# design.net
KiCad netlist of a schematic drawn in Altium Designer
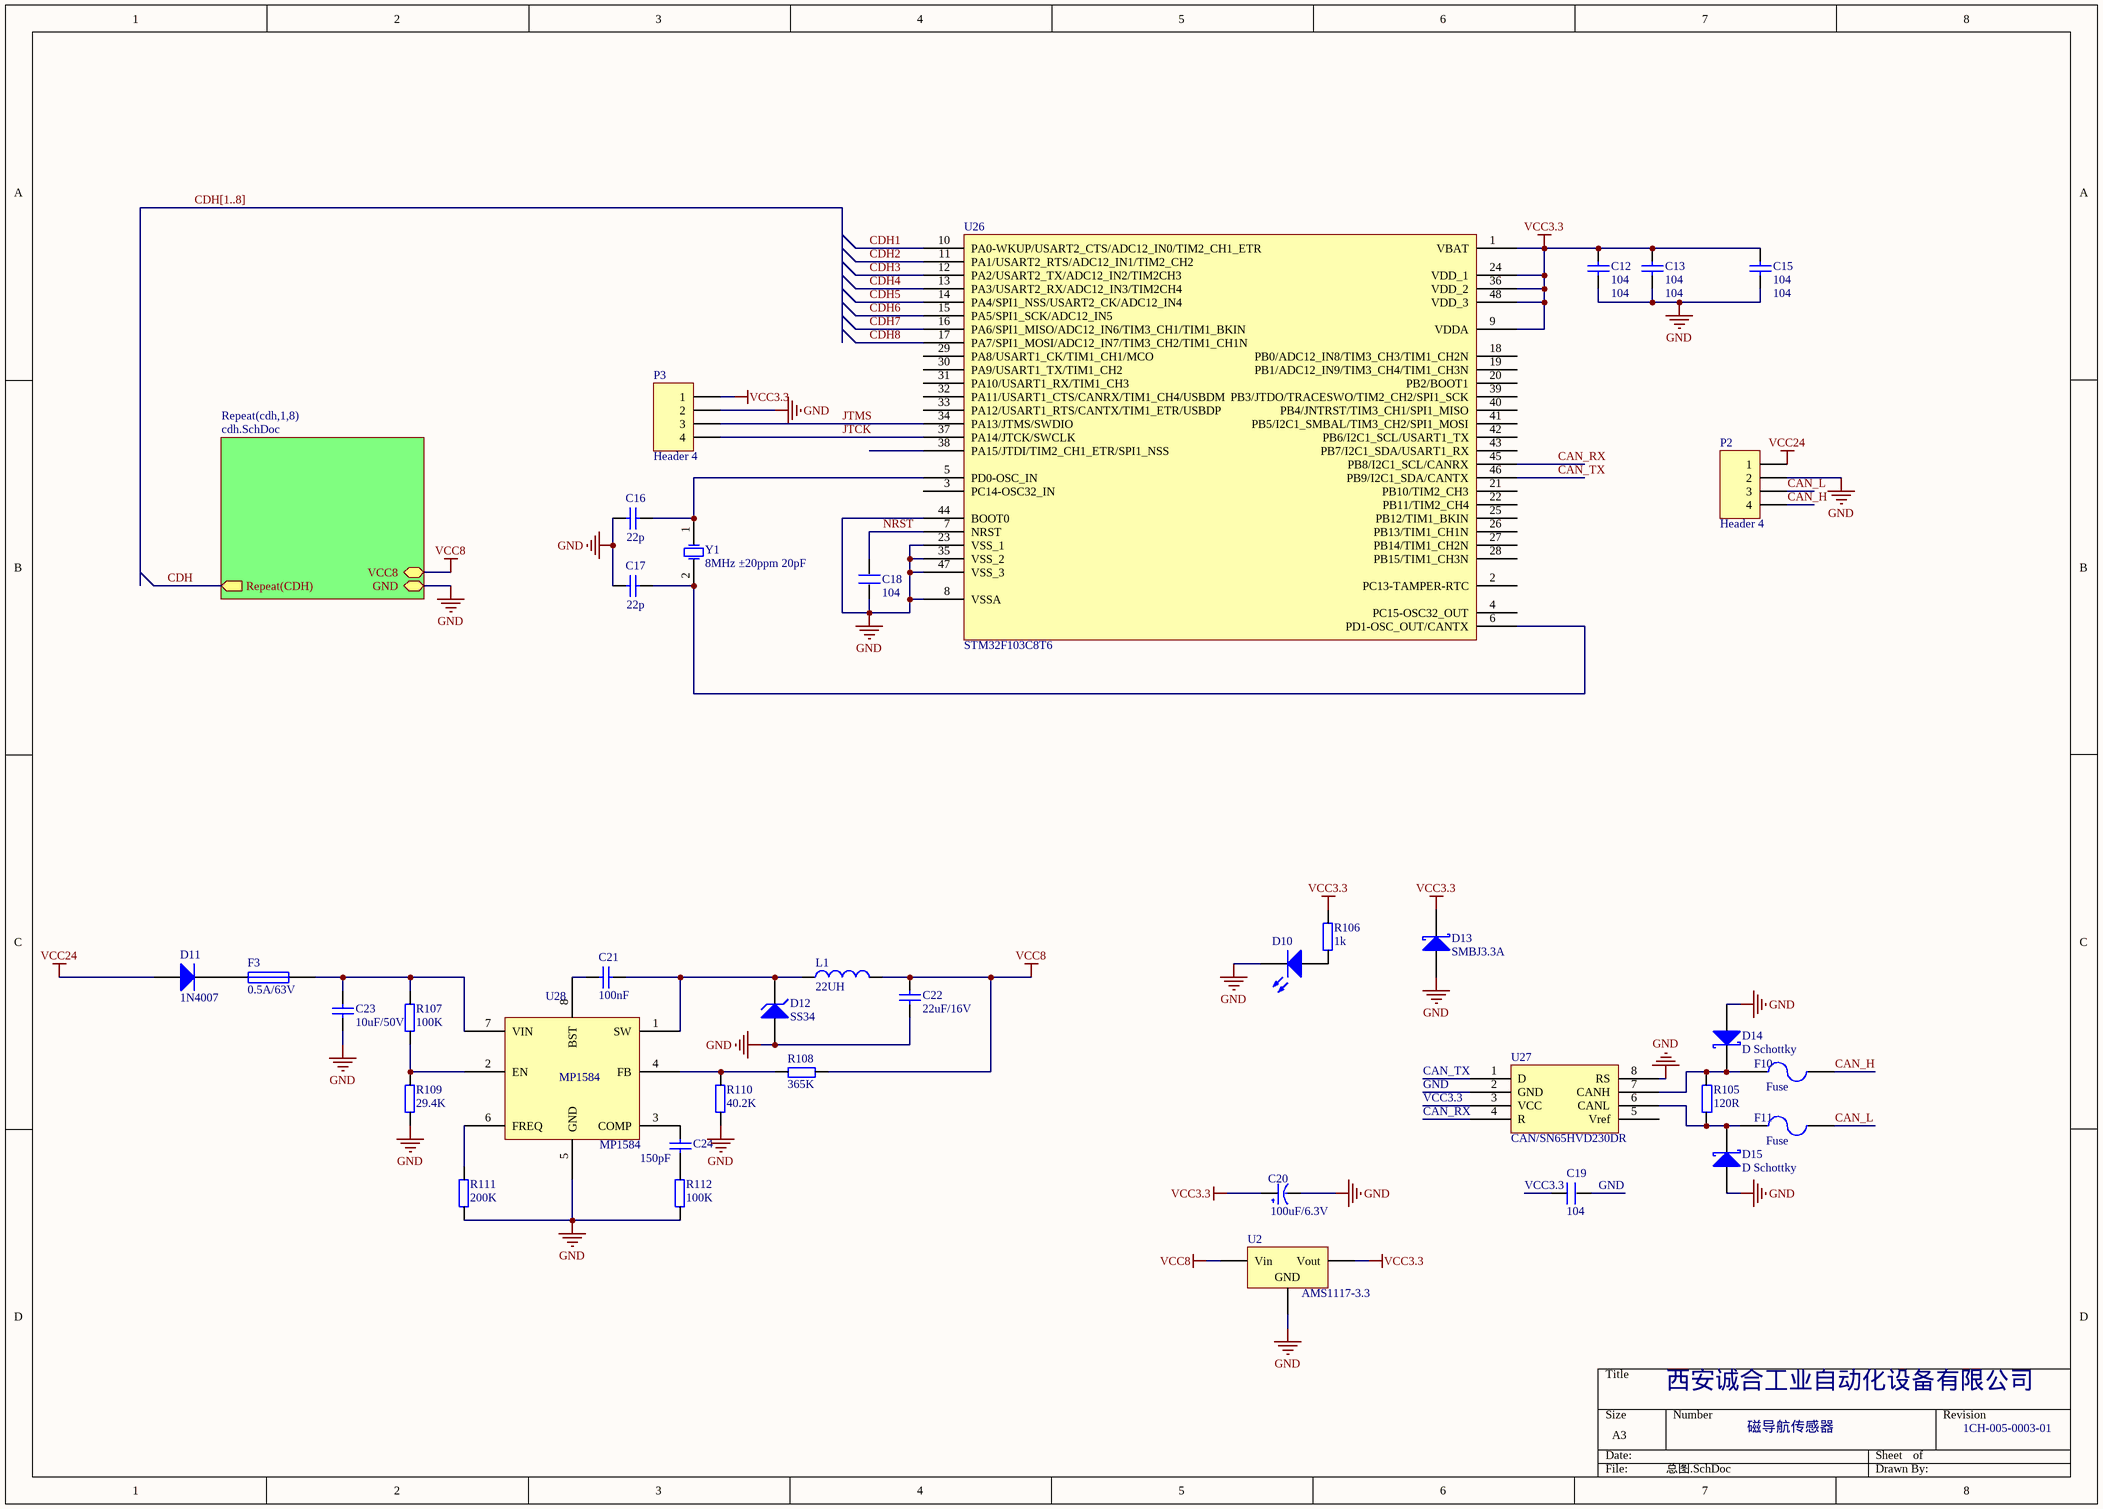
[diagram p0: 总图.SchDoc]

(export (version "E")
  (design (tool "Eeschema 10.0.6"))
  (components
    (comp (ref "C12")
      (value "104")
      (footprint "0603-CAP")
      (description "Capacitor")
      (fields (field (name "ALTIUM_VALUE") "104") (field (name "PUBLISHER") "Altium Limited"))
      (libsource (lib "Miscellaneous Devices") (part "Cap"))
    )
    (comp (ref "C13")
      (value "104")
      (footprint "0603-CAP")
      (description "Capacitor")
      (fields (field (name "ALTIUM_VALUE") "104") (field (name "PUBLISHER") "Altium Limited"))
      (libsource (lib "Miscellaneous Devices") (part "Cap"))
    )
    (comp (ref "C15")
      (value "104")
      (footprint "0603-CAP")
      (description "Capacitor")
      (fields (field (name "ALTIUM_VALUE") "104") (field (name "PUBLISHER") "Altium Limited"))
      (libsource (lib "Miscellaneous Devices") (part "Cap"))
    )
    (comp (ref "C16")
      (value "22p")
      (footprint "0603-CAP")
      (description "Capacitor")
      (fields (field (name "PUBLISHER") "Altium Limited"))
      (libsource (lib "Miscellaneous Devices") (part "Cap"))
    )
    (comp (ref "C17")
      (value "22p")
      (footprint "0603-CAP")
      (description "Capacitor")
      (fields (field (name "PUBLISHER") "Altium Limited"))
      (libsource (lib "Miscellaneous Devices") (part "Cap"))
    )
    (comp (ref "C18")
      (value "104")
      (footprint "0603-CAP")
      (libsource (lib "Explorer STM32F407封装库") (part "C"))
    )
    (comp (ref "C19")
      (value "104")
      (footprint "0603-CAP")
      (libsource (lib "Explorer STM32F407封装库") (part "C_3"))
    )
    (comp (ref "C20") (value "100uF/6.3V") (footprint "3216") (libsource (lib "WarShip V3_SCH") (part "CAP")))
    (comp (ref "C21")
      (value "100nF")
      (footprint "0603-CAP")
      (description "Capacitor (Semiconductor SIM Model)")
      (fields (field (name "Comment") "0.1uF") (field (name "PUBLISHER") "Altium Limited"))
      (libsource (lib "Miscellaneous Devices") (part "Cap Semi"))
    )
    (comp (ref "C22")
      (value "22uF/16V")
      (footprint "1206")
      (description "Capacitor (Semiconductor SIM Model)")
      (fields (field (name "PUBLISHER") "Altium Limited"))
      (libsource (lib "Miscellaneous Devices") (part "Cap Semi"))
    )
    (comp (ref "C23")
      (value "10uF/50V")
      (footprint "1206")
      (description "Capacitor (Semiconductor SIM Model)")
      (fields (field (name "PUBLISHER") "Altium Limited"))
      (libsource (lib "Miscellaneous Devices") (part "Cap Semi"))
    )
    (comp (ref "C24")
      (value "150pF")
      (footprint "0603-CAP")
      (description "Capacitor (Semiconductor SIM Model)")
      (fields (field (name "Comment") "0.1uF") (field (name "PUBLISHER") "Altium Limited"))
      (libsource (lib "Miscellaneous Devices") (part "Cap Semi"))
    )
    (comp (ref "D10")
      (value "LED0")
      (footprint "LC-0805_LED_S1")
      (description "Typical INFRARED GaAs LED")
      (fields (field (name "PUBLISHER") "Altium Limited"))
      (libsource (lib "继电器板_1") (part "LED0"))
    )
    (comp (ref "D11")
      (value "1N4007")
      (footprint "SMA(DO-214AC)_S1")
      (description "Default Diode")
      (fields (field (name "PUBLISHER") "Altium Limited"))
      (libsource (lib "Miscellaneous Devices") (part "Diode"))
    )
    (comp (ref "D12")
      (value "SS34")
      (footprint "SMA(DO-214AC)_S1")
      (description "Zener Diode")
      (fields (field (name "PUBLISHER") "Altium Limited"))
      (libsource (lib "Miscellaneous Devices") (part "D Zener"))
    )
    (comp (ref "D13")
      (value "SMBJ3.3A")
      (footprint "SMB(DO-214AA)_S1")
      (description "Schottky Rectifier")
      (fields (field (name "PUBLISHER") "Altium Limited"))
      (libsource (lib "Miscellaneous Devices") (part "Diode 18TQ045"))
    )
    (comp (ref "D14")
      (value "D Schottky")
      (footprint "SMB")
      (description "Schottky Diode")
      (fields (field (name "PUBLISHER") "Altium Limited"))
      (libsource (lib "Miscellaneous Devices") (part "D Schottky"))
    )
    (comp (ref "D15")
      (value "D Schottky")
      (footprint "SMB")
      (description "Schottky Diode")
      (fields (field (name "PUBLISHER") "Altium Limited"))
      (libsource (lib "Miscellaneous Devices") (part "D Schottky"))
    )
    (comp (ref "F3")
      (value "0.5A/63V")
      (footprint "1206")
      (description "Fuse")
      (fields (field (name "PUBLISHER") "Altium Limited"))
      (libsource (lib "Miscellaneous Devices") (part "Fuse 1"))
    )
    (comp (ref "F10")
      (value "Fuse")
      (footprint "12Z-2010")
      (fields (field (name "PUBLISHER") "Altium Limited"))
      (libsource (lib "Miscellaneous Devices") (part "Fuse 2"))
    )
    (comp (ref "F11")
      (value "Fuse")
      (footprint "12Z-2010")
      (fields (field (name "PUBLISHER") "Altium Limited"))
      (libsource (lib "Miscellaneous Devices") (part "Fuse 2"))
    )
    (comp (ref "L1")
      (value "22UH")
      (footprint "L-7*7*4mm-S")
      (description "Inductor")
      (fields (field (name "PUBLISHER") "Altium Limited"))
      (libsource (lib "Miscellaneous Devices") (part "Inductor"))
    )
    (comp (ref "P2")
      (value "Header 4")
      (footprint "DZ-4-3.5")
      (description "Header, 4-Pin")
      (fields (field (name "PUBLISHER") "Altium Limited"))
      (libsource (lib "Miscellaneous Connectors") (part "Header 4"))
    )
    (comp (ref "P3")
      (value "Header 4")
      (footprint "HDR1X4")
      (description "Header, 4-Pin")
      (fields (field (name "PUBLISHER") "Altium Limited"))
      (libsource (lib "Miscellaneous Connectors") (part "Header 4"))
    )
    (comp (ref "R105")
      (value "120R")
      (footprint "0805_R")
      (libsource (lib "Explorer STM32F407封装库") (part "R_2"))
    )
    (comp (ref "R106") (value "1k") (footprint "0603") (libsource (lib "Explorer STM32F407封装库") (part "R_2")))
    (comp (ref "R107")
      (value "100K")
      (footprint "0603")
      (libsource (lib "Explorer STM32F407封装库") (part "R_2"))
    )
    (comp (ref "R108")
      (value "365K")
      (footprint "0603")
      (libsource (lib "Explorer STM32F407封装库") (part "R_2"))
    )
    (comp (ref "R109")
      (value "29.4K")
      (footprint "0603")
      (libsource (lib "Explorer STM32F407封装库") (part "R_2"))
    )
    (comp (ref "R110")
      (value "40.2K")
      (footprint "0603")
      (libsource (lib "Explorer STM32F407封装库") (part "R_2"))
    )
    (comp (ref "R111")
      (value "200K")
      (footprint "0603")
      (libsource (lib "Explorer STM32F407封装库") (part "R_2"))
    )
    (comp (ref "R112")
      (value "100K")
      (footprint "0603")
      (libsource (lib "Explorer STM32F407封装库") (part "R_2"))
    )
    (comp (ref "U2")
      (value "AMS1117-3.3")
      (footprint "SOT-223")
      (description "低压差线性稳压(LDO)")
      (libsource (lib "Miscellaneous Devices LC") (part "SOT-223 AMS1117-3.3"))
    )
    (comp (ref "U26")
      (value "STM32F103C8T6")
      (footprint "LC-LQFP-48")
      (libsource (lib "Schlib1") (part "stm32f103v8t6"))
    )
    (comp (ref "U27")
      (value "CAN/SN65HVD230DR")
      (footprint "SOIC-8_150mil")
      (description "CAN")
      (libsource (lib "Miscellaneous Devices LC") (part "CAN/SN65HVD230DR_[C12084]"))
    )
    (comp (ref "U28") (value "MP1584") (footprint "SO-8") (libsource (lib "磁导航") (part "MP1584EN")))
    (comp (ref "Y1")
      (value "8MHz ±20ppm 20pF")
      (footprint "SMD-5032_2P")
      (description "贴片晶振")
      (libsource (lib "Miscellaneous Devices LC") (part "SMD-5032_2P 8MHz 20ppm 20pF"))
    )
  )
  (nets
    (net (code "1") (name "/CAN_H") (class "Default")
      (node (ref "F10") (pin "1") (pinfunction "1_1") (pintype "passive"))
      (node (ref "P2") (pin "4") (pinfunction "4_4") (pintype "passive"))
    )
    (net (code "2") (name "/CAN_L") (class "Default")
      (node (ref "F11") (pin "1") (pinfunction "1_1") (pintype "passive"))
      (node (ref "P2") (pin "3") (pinfunction "3_3") (pintype "passive"))
    )
    (net (code "3") (name "/CAN_RX") (class "Default")
      (node (ref "U26") (pin "45") (pinfunction "PB8/I2C1_SCL/CANRX_45") (pintype "passive"))
      (node (ref "U27") (pin "4") (pinfunction "R_4") (pintype "passive"))
    )
    (net (code "4") (name "/CAN_TX") (class "Default")
      (node (ref "U26") (pin "46") (pinfunction "PB9/I2C1_SDA/CANTX_46") (pintype "passive"))
      (node (ref "U27") (pin "1") (pinfunction "D_1") (pintype "passive"))
    )
    (net (code "6") (name "/CDH1") (class "Default")
      (node (ref "U26") (pin "10") (pinfunction "PA0-WKUP/USART2_CTS/ADC12_IN0/TIM2_CH1_ETR_10") (pintype "passive"))
    )
    (net (code "7") (name "/CDH2") (class "Default")
      (node (ref "U26") (pin "11") (pinfunction "PA1/USART2_RTS/ADC12_IN1/TIM2_CH2_11") (pintype "passive"))
    )
    (net (code "8") (name "/CDH3") (class "Default")
      (node (ref "U26") (pin "12") (pinfunction "PA2/USART2_TX/ADC12_IN2/TIM2CH3_12") (pintype "passive"))
    )
    (net (code "9") (name "/CDH4") (class "Default")
      (node (ref "U26") (pin "13") (pinfunction "PA3/USART2_RX/ADC12_IN3/TIM2CH4_13") (pintype "passive"))
    )
    (net (code "10") (name "/CDH5") (class "Default")
      (node (ref "U26") (pin "14") (pinfunction "PA4/SPI1_NSS/USART2_CK/ADC12_IN4_14") (pintype "passive"))
    )
    (net (code "11") (name "/CDH6") (class "Default")
      (node (ref "U26") (pin "15") (pinfunction "PA5/SPI1_SCK/ADC12_IN5_15") (pintype "passive"))
    )
    (net (code "12") (name "/CDH7") (class "Default")
      (node (ref "U26") (pin "16") (pinfunction "PA6/SPI1_MISO/ADC12_IN6/TIM3_CH1/TIM1_BKIN_16") (pintype "passive"))
    )
    (net (code "13") (name "/CDH8") (class "Default")
      (node (ref "U26") (pin "17") (pinfunction "PA7/SPI1_MOSI/ADC12_IN7/TIM3_CH2/TIM1_CH1N_17") (pintype "passive"))
    )
    (net (code "15") (name "/JTCK") (class "Default")
      (node (ref "P3") (pin "4") (pinfunction "4_4") (pintype "passive"))
      (node (ref "U26") (pin "37") (pinfunction "PA14/JTCK/SWCLK_37") (pintype "passive"))
    )
    (net (code "16") (name "/JTMS") (class "Default")
      (node (ref "P3") (pin "3") (pinfunction "3_3") (pintype "passive"))
      (node (ref "U26") (pin "34") (pinfunction "PA13/JTMS/SWDIO_34") (pintype "passive"))
    )
    (net (code "17") (name "/NRST") (class "Default")
      (node (ref "C18") (pin "2") (pintype "passive"))
      (node (ref "U26") (pin "7") (pinfunction "NRST_7") (pintype "passive"))
    )
    (net (code "18") (name "GND") (class "Default")
      (node (ref "C12") (pin "2") (pinfunction "2_2") (pintype "passive"))
      (node (ref "C13") (pin "2") (pinfunction "2_2") (pintype "passive"))
      (node (ref "C15") (pin "2") (pinfunction "2_2") (pintype "passive"))
      (node (ref "C16") (pin "2") (pinfunction "2_2") (pintype "passive"))
      (node (ref "C17") (pin "2") (pinfunction "2_2") (pintype "passive"))
      (node (ref "C18") (pin "1") (pintype "passive"))
      (node (ref "C19") (pin "2") (pintype "passive"))
      (node (ref "C20") (pin "2") (pinfunction "GND_2") (pintype "passive"))
      (node (ref "C22") (pin "1") (pinfunction "1_1") (pintype "passive"))
      (node (ref "C23") (pin "2") (pinfunction "2_2") (pintype "passive"))
      (node (ref "D10") (pin "K") (pinfunction "K_K") (pintype "passive"))
      (node (ref "D12") (pin "1") (pinfunction "A_1") (pintype "passive"))
      (node (ref "D13") (pin "2") (pinfunction "A_2") (pintype "passive"))
      (node (ref "D14") (pin "1") (pinfunction "A_1") (pintype "passive"))
      (node (ref "D15") (pin "1") (pinfunction "A_1") (pintype "passive"))
      (node (ref "P2") (pin "2") (pinfunction "2_2") (pintype "passive"))
      (node (ref "P3") (pin "2") (pinfunction "2_2") (pintype "passive"))
      (node (ref "R109") (pin "2") (pintype "passive"))
      (node (ref "R110") (pin "2") (pintype "passive"))
      (node (ref "R111") (pin "2") (pintype "passive"))
      (node (ref "R112") (pin "2") (pintype "passive"))
      (node (ref "U2") (pin "1") (pinfunction "GND_1") (pintype "passive"))
      (node (ref "U26") (pin "23") (pinfunction "VSS_1_23") (pintype "passive"))
      (node (ref "U26") (pin "35") (pinfunction "VSS_2_35") (pintype "passive"))
      (node (ref "U26") (pin "44") (pinfunction "BOOT0_44") (pintype "passive"))
      (node (ref "U26") (pin "47") (pinfunction "VSS_3_47") (pintype "passive"))
      (node (ref "U26") (pin "8") (pinfunction "VSSA_8") (pintype "passive"))
      (node (ref "U27") (pin "2") (pinfunction "GND_2") (pintype "passive"))
      (node (ref "U27") (pin "8") (pinfunction "RS_8") (pintype "passive"))
      (node (ref "U28") (pin "5") (pinfunction "GND_5") (pintype "passive"))
    )
    (net (code "19") (name "Net-(C24-Pad1)") (class "Default")
      (node (ref "C24") (pin "1") (pinfunction "1_1") (pintype "passive"))
      (node (ref "R112") (pin "1") (pintype "passive"))
    )
    (net (code "20") (name "Net-(D10-PadA)") (class "Default")
      (node (ref "D10") (pin "A") (pinfunction "A_A") (pintype "passive"))
      (node (ref "R106") (pin "2") (pintype "passive"))
    )
    (net (code "21") (name "Net-(D11-K)") (class "Default")
      (node (ref "D11") (pin "2") (pinfunction "K_2") (pintype "passive"))
      (node (ref "F3") (pin "1") (pinfunction "1_1") (pintype "passive"))
    )
    (net (code "22") (name "Net-(D12-K)") (class "Default")
      (node (ref "C21") (pin "1") (pinfunction "1_1") (pintype "passive"))
      (node (ref "D12") (pin "2") (pinfunction "K_2") (pintype "passive"))
      (node (ref "L1") (pin "1") (pinfunction "1_1") (pintype "passive"))
      (node (ref "U28") (pin "1") (pinfunction "SW_1") (pintype "passive"))
    )
    (net (code "23") (name "Net-(D14-K)") (class "Default")
      (node (ref "D14") (pin "2") (pinfunction "K_2") (pintype "passive"))
      (node (ref "F10") (pin "2") (pinfunction "2_2") (pintype "passive"))
      (node (ref "R105") (pin "2") (pintype "passive"))
      (node (ref "U27") (pin "7") (pinfunction "CANH_7") (pintype "passive"))
    )
    (net (code "24") (name "Net-(D15-K)") (class "Default")
      (node (ref "D15") (pin "2") (pinfunction "K_2") (pintype "passive"))
      (node (ref "F11") (pin "2") (pinfunction "2_2") (pintype "passive"))
      (node (ref "R105") (pin "1") (pintype "passive"))
      (node (ref "U27") (pin "6") (pinfunction "CANL_6") (pintype "passive"))
    )
    (net (code "25") (name "Net-(U26-PD0-OSC_IN)") (class "Default")
      (node (ref "C16") (pin "1") (pinfunction "1_1") (pintype "passive"))
      (node (ref "U26") (pin "5") (pinfunction "PD0-OSC_IN_5") (pintype "passive"))
      (node (ref "Y1") (pin "1") (pinfunction "OSC1_1") (pintype "passive"))
    )
    (net (code "26") (name "Net-(U26-PD1-OSC_OUT{slash}CANTX)") (class "Default")
      (node (ref "C17") (pin "1") (pinfunction "1_1") (pintype "passive"))
      (node (ref "U26") (pin "6") (pinfunction "PD1-OSC_OUT/CANTX_6") (pintype "passive"))
      (node (ref "Y1") (pin "2") (pinfunction "OSC2_2") (pintype "passive"))
    )
    (net (code "27") (name "Net-(U28-BST)") (class "Default")
      (node (ref "C21") (pin "2") (pinfunction "2_2") (pintype "passive"))
      (node (ref "U28") (pin "8") (pinfunction "BST_8") (pintype "passive"))
    )
    (net (code "28") (name "Net-(U28-COMP)") (class "Default")
      (node (ref "C24") (pin "2") (pinfunction "2_2") (pintype "passive"))
      (node (ref "U28") (pin "3") (pinfunction "COMP_3") (pintype "passive"))
    )
    (net (code "29") (name "Net-(U28-EN)") (class "Default")
      (node (ref "R107") (pin "2") (pintype "passive"))
      (node (ref "R109") (pin "1") (pintype "passive"))
      (node (ref "U28") (pin "2") (pinfunction "EN_2") (pintype "passive"))
    )
    (net (code "30") (name "Net-(U28-FB)") (class "Default")
      (node (ref "R108") (pin "1") (pintype "passive"))
      (node (ref "R110") (pin "1") (pintype "passive"))
      (node (ref "U28") (pin "4") (pinfunction "FB_4") (pintype "passive"))
    )
    (net (code "31") (name "Net-(U28-FREQ)") (class "Default")
      (node (ref "R111") (pin "1") (pintype "passive"))
      (node (ref "U28") (pin "6") (pinfunction "FREQ_6") (pintype "passive"))
    )
    (net (code "32") (name "Net-(U28-VIN)") (class "Default")
      (node (ref "C23") (pin "1") (pinfunction "1_1") (pintype "passive"))
      (node (ref "F3") (pin "2") (pinfunction "2_2") (pintype "passive"))
      (node (ref "R107") (pin "1") (pintype "passive"))
      (node (ref "U28") (pin "7") (pinfunction "VIN_7") (pintype "passive"))
    )
    (net (code "33") (name "VCC3.3") (class "Default")
      (node (ref "C12") (pin "1") (pinfunction "1_1") (pintype "passive"))
      (node (ref "C13") (pin "1") (pinfunction "1_1") (pintype "passive"))
      (node (ref "C15") (pin "1") (pinfunction "1_1") (pintype "passive"))
      (node (ref "C19") (pin "1") (pintype "passive"))
      (node (ref "C20") (pin "1") (pinfunction "VCC_1") (pintype "passive"))
      (node (ref "D13") (pin "1") (pinfunction "K_1") (pintype "passive"))
      (node (ref "P3") (pin "1") (pinfunction "1_1") (pintype "passive"))
      (node (ref "R106") (pin "1") (pintype "passive"))
      (node (ref "U2") (pin "2") (pinfunction "Vout_2") (pintype "passive"))
      (node (ref "U26") (pin "1") (pinfunction "VBAT_1") (pintype "passive"))
      (node (ref "U26") (pin "24") (pinfunction "VDD_1_24") (pintype "passive"))
      (node (ref "U26") (pin "36") (pinfunction "VDD_2_36") (pintype "passive"))
      (node (ref "U26") (pin "48") (pinfunction "VDD_3_48") (pintype "passive"))
      (node (ref "U26") (pin "9") (pinfunction "VDDA_9") (pintype "passive"))
      (node (ref "U27") (pin "3") (pinfunction "VCC_3") (pintype "passive"))
    )
    (net (code "34") (name "VCC8") (class "Default")
      (node (ref "C22") (pin "2") (pinfunction "2_2") (pintype "passive"))
      (node (ref "L1") (pin "2") (pinfunction "2_2") (pintype "passive"))
      (node (ref "R108") (pin "2") (pintype "passive"))
      (node (ref "U2") (pin "3") (pinfunction "Vin_3") (pintype "passive"))
    )
    (net (code "35") (name "VCC24") (class "Default")
      (node (ref "D11") (pin "1") (pinfunction "A_1") (pintype "passive"))
      (node (ref "P2") (pin "1") (pinfunction "1_1") (pintype "passive"))
    )
    (net (code "36") (name "unconnected-(U26-PA8{slash}USART1_CK{slash}TIM1_CH1{slash}MCO-Pad29)") (class "Default")
      (node (ref "U26") (pin "29") (pinfunction "PA8/USART1_CK/TIM1_CH1/MCO_29") (pintype "passive"))
    )
    (net (code "37") (name "unconnected-(U26-PA9{slash}USART1_TX{slash}TIM1_CH2-Pad30)") (class "Default")
      (node (ref "U26") (pin "30") (pinfunction "PA9/USART1_TX/TIM1_CH2_30") (pintype "passive"))
    )
    (net (code "38") (name "unconnected-(U26-PA10{slash}USART1_RX{slash}TIM1_CH3-Pad31)") (class "Default")
      (node (ref "U26") (pin "31") (pinfunction "PA10/USART1_RX/TIM1_CH3_31") (pintype "passive"))
    )
    (net (code "39") (name "unconnected-(U26-PA11{slash}USART1_CTS{slash}CANRX{slash}TIM1_CH4{slash}USBDM-Pad32)") (class "Default")
      (node (ref "U26") (pin "32") (pinfunction "PA11/USART1_CTS/CANRX/TIM1_CH4/USBDM_32") (pintype "passive"))
    )
    (net (code "40") (name "unconnected-(U26-PA12{slash}USART1_RTS{slash}CANTX{slash}TIM1_ETR{slash}USBDP-Pad33)") (class "Default")
      (node (ref "U26") (pin "33") (pinfunction "PA12/USART1_RTS/CANTX/TIM1_ETR/USBDP_33") (pintype "passive"))
    )
    (net (code "41") (name "unconnected-(U26-PA15{slash}JTDI{slash}TIM2_CH1_ETR{slash}SPI1_NSS-Pad38)") (class "Default")
      (node (ref "U26") (pin "38") (pinfunction "PA15/JTDI/TIM2_CH1_ETR/SPI1_NSS_38") (pintype "passive"))
    )
    (net (code "42") (name "unconnected-(U26-PB0{slash}ADC12_IN8{slash}TIM3_CH3{slash}TIM1_CH2N-Pad18)") (class "Default")
      (node (ref "U26") (pin "18") (pinfunction "PB0/ADC12_IN8/TIM3_CH3/TIM1_CH2N_18") (pintype "passive"))
    )
    (net (code "43") (name "unconnected-(U26-PB1{slash}ADC12_IN9{slash}TIM3_CH4{slash}TIM1_CH3N-Pad19)") (class "Default")
      (node (ref "U26") (pin "19") (pinfunction "PB1/ADC12_IN9/TIM3_CH4/TIM1_CH3N_19") (pintype "passive"))
    )
    (net (code "44") (name "unconnected-(U26-PB2{slash}BOOT1-Pad20)") (class "Default")
      (node (ref "U26") (pin "20") (pinfunction "PB2/BOOT1_20") (pintype "passive"))
    )
    (net (code "45") (name "unconnected-(U26-PB3{slash}JTDO{slash}TRACESWO{slash}TIM2_CH2{slash}SPI1_SCK-Pad39)") (class "Default")
      (node (ref "U26") (pin "39") (pinfunction "PB3/JTDO/TRACESWO/TIM2_CH2/SPI1_SCK_39") (pintype "passive"))
    )
    (net (code "46") (name "unconnected-(U26-PB4{slash}JNTRST{slash}TIM3_CH1{slash}SPI1_MISO-Pad40)") (class "Default")
      (node (ref "U26") (pin "40") (pinfunction "PB4/JNTRST/TIM3_CH1/SPI1_MISO_40") (pintype "passive"))
    )
    (net (code "47") (name "unconnected-(U26-PB5{slash}I2C1_SMBAL{slash}TIM3_CH2{slash}SPI1_MOSI-Pad41)") (class "Default")
      (node (ref "U26") (pin "41") (pinfunction "PB5/I2C1_SMBAL/TIM3_CH2/SPI1_MOSI_41") (pintype "passive"))
    )
    (net (code "48") (name "unconnected-(U26-PB6{slash}I2C1_SCL{slash}USART1_TX-Pad42)") (class "Default")
      (node (ref "U26") (pin "42") (pinfunction "PB6/I2C1_SCL/USART1_TX_42") (pintype "passive"))
    )
    (net (code "49") (name "unconnected-(U26-PB7{slash}I2C1_SDA{slash}USART1_RX-Pad43)") (class "Default")
      (node (ref "U26") (pin "43") (pinfunction "PB7/I2C1_SDA/USART1_RX_43") (pintype "passive"))
    )
    (net (code "50") (name "unconnected-(U26-PB10{slash}TIM2_CH3-Pad21)") (class "Default")
      (node (ref "U26") (pin "21") (pinfunction "PB10/TIM2_CH3_21") (pintype "passive"))
    )
    (net (code "51") (name "unconnected-(U26-PB11{slash}TIM2_CH4-Pad22)") (class "Default")
      (node (ref "U26") (pin "22") (pinfunction "PB11/TIM2_CH4_22") (pintype "passive"))
    )
    (net (code "52") (name "unconnected-(U26-PB12{slash}TIM1_BKIN-Pad25)") (class "Default")
      (node (ref "U26") (pin "25") (pinfunction "PB12/TIM1_BKIN_25") (pintype "passive"))
    )
    (net (code "53") (name "unconnected-(U26-PB13{slash}TIM1_CH1N-Pad26)") (class "Default")
      (node (ref "U26") (pin "26") (pinfunction "PB13/TIM1_CH1N_26") (pintype "passive"))
    )
    (net (code "54") (name "unconnected-(U26-PB14{slash}TIM1_CH2N-Pad27)") (class "Default")
      (node (ref "U26") (pin "27") (pinfunction "PB14/TIM1_CH2N_27") (pintype "passive"))
    )
    (net (code "55") (name "unconnected-(U26-PB15{slash}TIM1_CH3N-Pad28)") (class "Default")
      (node (ref "U26") (pin "28") (pinfunction "PB15/TIM1_CH3N_28") (pintype "passive"))
    )
    (net (code "56") (name "unconnected-(U26-PC13-TAMPER-RTC-Pad2)") (class "Default")
      (node (ref "U26") (pin "2") (pinfunction "PC13-TAMPER-RTC_2") (pintype "passive"))
    )
    (net (code "57") (name "unconnected-(U26-PC14-OSC32_IN-Pad3)") (class "Default")
      (node (ref "U26") (pin "3") (pinfunction "PC14-OSC32_IN_3") (pintype "passive"))
    )
    (net (code "58") (name "unconnected-(U26-PC15-OSC32_OUT-Pad4)") (class "Default")
      (node (ref "U26") (pin "4") (pinfunction "PC15-OSC32_OUT_4") (pintype "passive"))
    )
    (net (code "59") (name "unconnected-(U27-Vref-Pad5)") (class "Default")
      (node (ref "U27") (pin "5") (pinfunction "Vref_5") (pintype "passive"))
    )
  )
)
